# ShineRider.net
KiCad netlist of a schematic drawn in Altium Designer
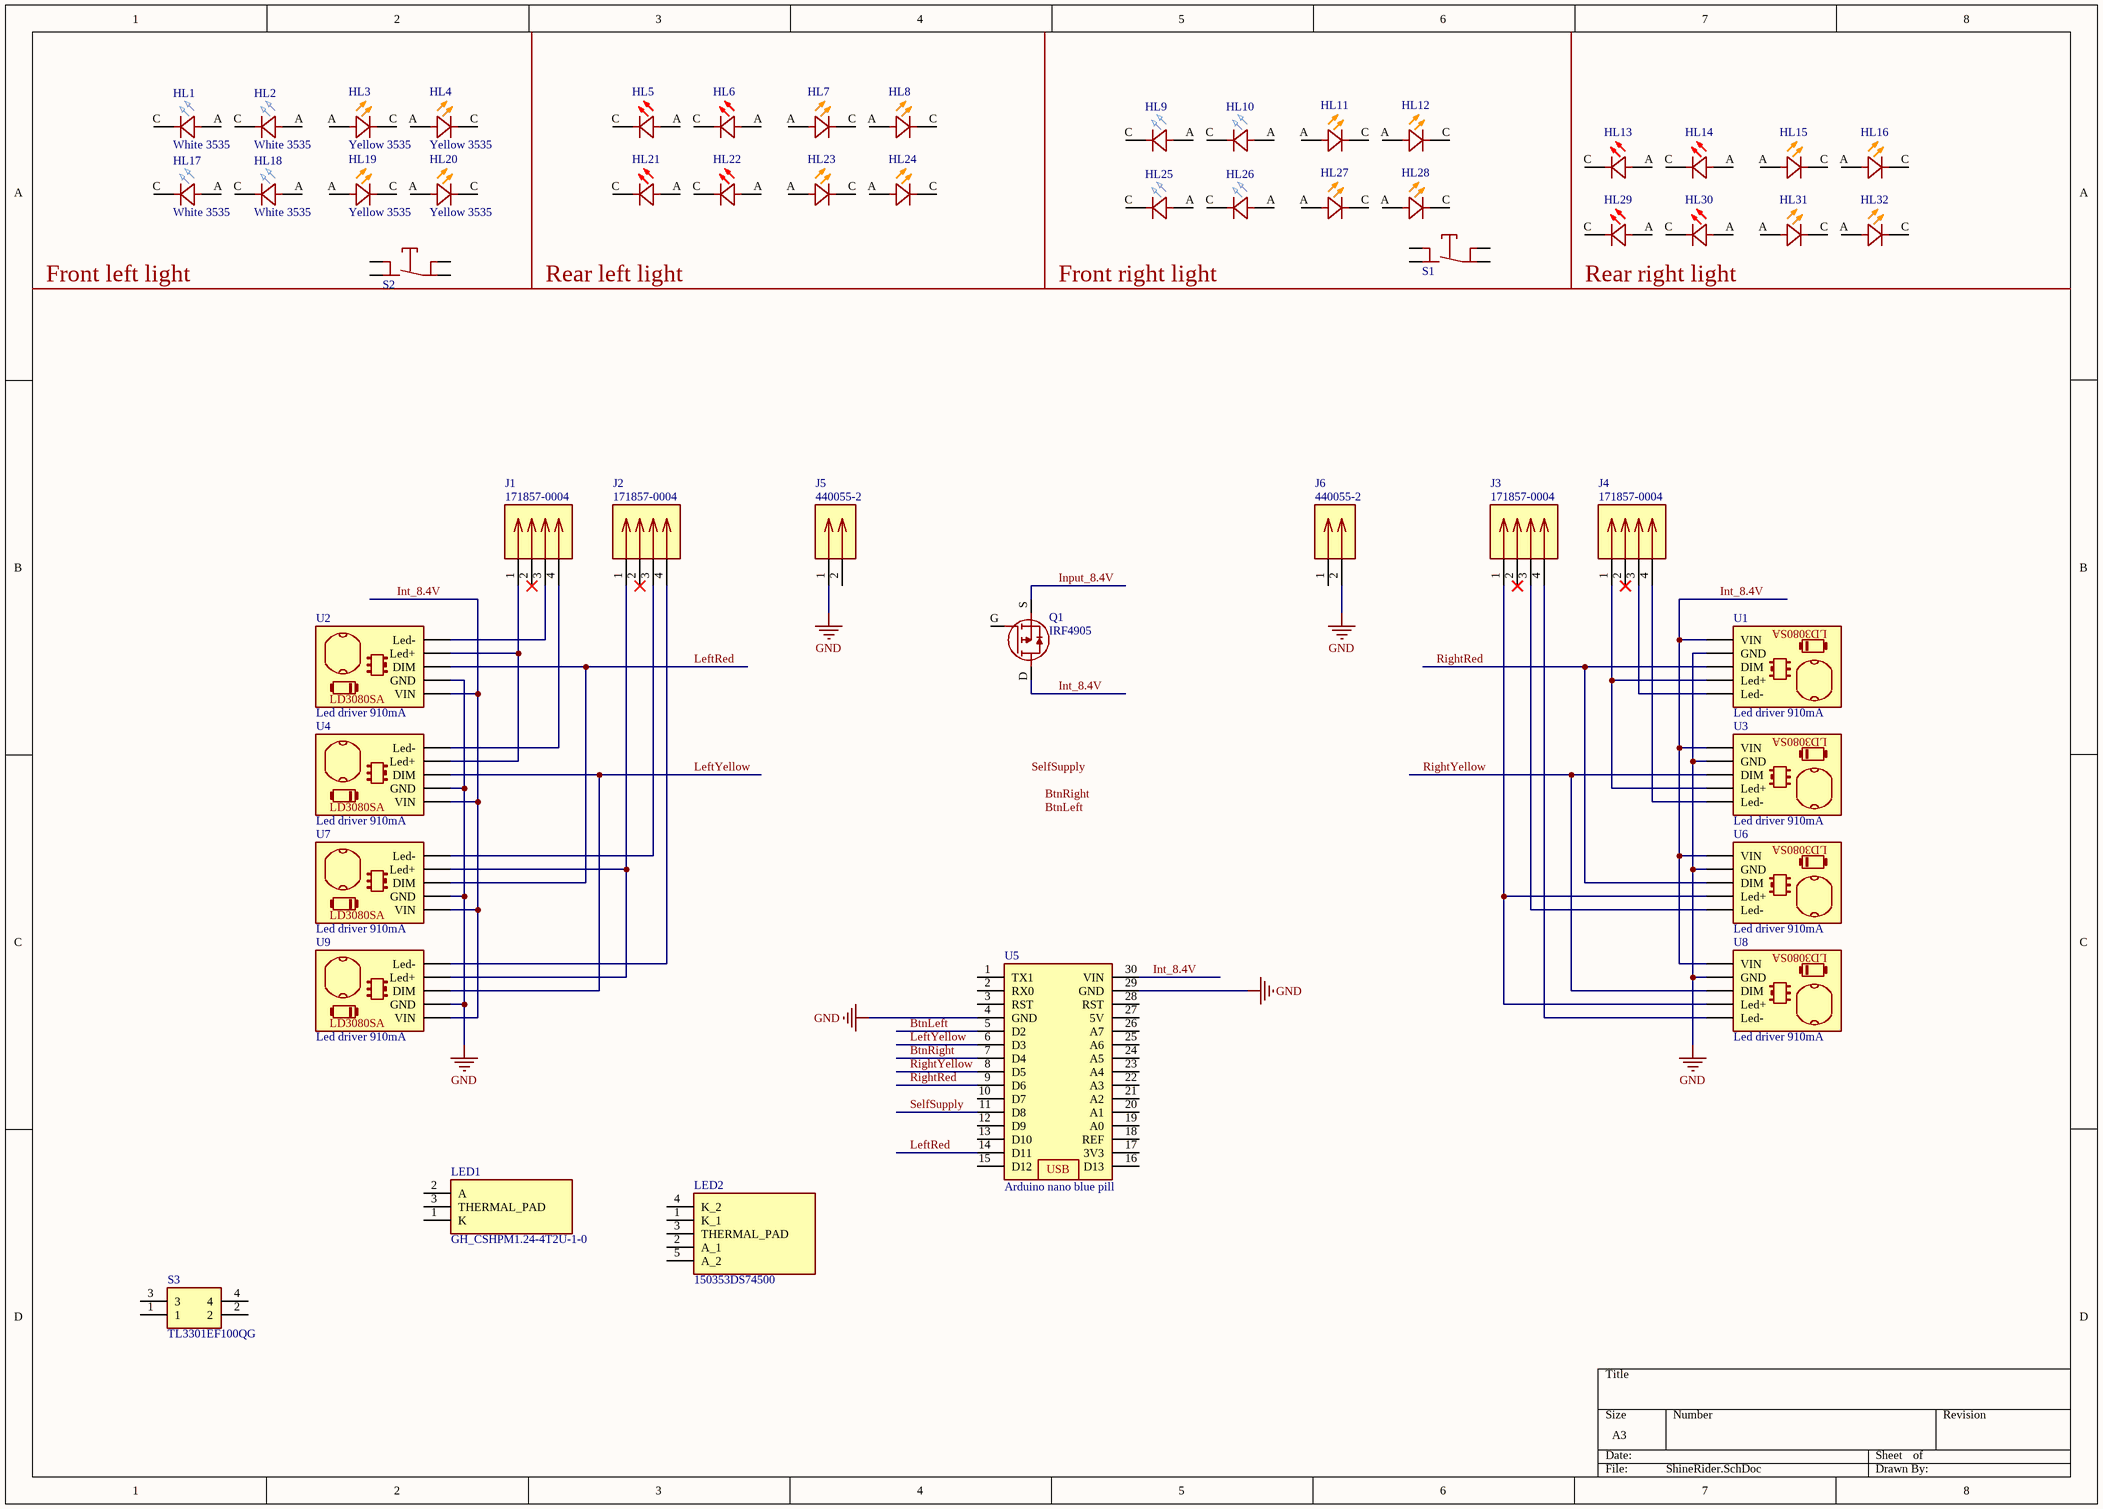
[diagram p0: ShineRider.SchDoc]

(export (version "E")
  (design (tool "Eeschema 10.0.6"))
  (components
    (comp (ref "HL1")
      (value "White 3535")
      (footprint "150353FS74500")
      (libsource (lib "SchComponents") (part "3535 white led"))
    )
    (comp (ref "HL2")
      (value "White 3535")
      (footprint "150353FS74500")
      (libsource (lib "SchComponents") (part "3535 white led"))
    )
    (comp (ref "HL3")
      (value "Yellow 3535")
      (footprint "150353FS74500")
      (libsource (lib "SchComponents") (part "3535 yellow led"))
    )
    (comp (ref "HL4")
      (value "Yellow 3535")
      (footprint "150353FS74500")
      (libsource (lib "SchComponents") (part "3535 yellow led"))
    )
    (comp (ref "HL5")
      (value "Red 3535")
      (footprint "150353FS74500")
      (libsource (lib "SchComponents") (part "3535 red led"))
    )
    (comp (ref "HL6")
      (value "Red 3535")
      (footprint "150353FS74500")
      (libsource (lib "SchComponents") (part "3535 red led"))
    )
    (comp (ref "HL7")
      (value "Yellow 3535")
      (footprint "150353FS74500")
      (libsource (lib "SchComponents") (part "3535 yellow led"))
    )
    (comp (ref "HL8")
      (value "Yellow 3535")
      (footprint "150353FS74500")
      (libsource (lib "SchComponents") (part "3535 yellow led"))
    )
    (comp (ref "HL9")
      (value "White 3535")
      (footprint "150353FS74500")
      (libsource (lib "SchComponents") (part "3535 white led"))
    )
    (comp (ref "HL10")
      (value "White 3535")
      (footprint "150353FS74500")
      (libsource (lib "SchComponents") (part "3535 white led"))
    )
    (comp (ref "HL11")
      (value "Yellow 3535")
      (footprint "150353FS74500")
      (libsource (lib "SchComponents") (part "3535 yellow led"))
    )
    (comp (ref "HL12")
      (value "Yellow 3535")
      (footprint "150353FS74500")
      (libsource (lib "SchComponents") (part "3535 yellow led"))
    )
    (comp (ref "HL13")
      (value "Red 3535")
      (footprint "150353FS74500")
      (libsource (lib "SchComponents") (part "3535 red led"))
    )
    (comp (ref "HL14")
      (value "Red 3535")
      (footprint "150353FS74500")
      (libsource (lib "SchComponents") (part "3535 red led"))
    )
    (comp (ref "HL15")
      (value "Yellow 3535")
      (footprint "150353FS74500")
      (libsource (lib "SchComponents") (part "3535 yellow led"))
    )
    (comp (ref "HL16")
      (value "Yellow 3535")
      (footprint "150353FS74500")
      (libsource (lib "SchComponents") (part "3535 yellow led"))
    )
    (comp (ref "HL17")
      (value "White 3535")
      (footprint "150353FS74500")
      (libsource (lib "SchComponents") (part "3535 white led"))
    )
    (comp (ref "HL18")
      (value "White 3535")
      (footprint "150353FS74500")
      (libsource (lib "SchComponents") (part "3535 white led"))
    )
    (comp (ref "HL19")
      (value "Yellow 3535")
      (footprint "150353FS74500")
      (libsource (lib "SchComponents") (part "3535 yellow led"))
    )
    (comp (ref "HL20")
      (value "Yellow 3535")
      (footprint "150353FS74500")
      (libsource (lib "SchComponents") (part "3535 yellow led"))
    )
    (comp (ref "HL21")
      (value "Red 3535")
      (footprint "150353FS74500")
      (libsource (lib "SchComponents") (part "3535 red led"))
    )
    (comp (ref "HL22")
      (value "Red 3535")
      (footprint "150353FS74500")
      (libsource (lib "SchComponents") (part "3535 red led"))
    )
    (comp (ref "HL23")
      (value "Yellow 3535")
      (footprint "150353FS74500")
      (libsource (lib "SchComponents") (part "3535 yellow led"))
    )
    (comp (ref "HL24")
      (value "Yellow 3535")
      (footprint "150353FS74500")
      (libsource (lib "SchComponents") (part "3535 yellow led"))
    )
    (comp (ref "HL25")
      (value "White 3535")
      (footprint "150353FS74500")
      (libsource (lib "SchComponents") (part "3535 white led"))
    )
    (comp (ref "HL26")
      (value "White 3535")
      (footprint "150353FS74500")
      (libsource (lib "SchComponents") (part "3535 white led"))
    )
    (comp (ref "HL27")
      (value "Yellow 3535")
      (footprint "150353FS74500")
      (libsource (lib "SchComponents") (part "3535 yellow led"))
    )
    (comp (ref "HL28")
      (value "Yellow 3535")
      (footprint "150353FS74500")
      (libsource (lib "SchComponents") (part "3535 yellow led"))
    )
    (comp (ref "HL29")
      (value "Red 3535")
      (footprint "150353FS74500")
      (libsource (lib "SchComponents") (part "3535 red led"))
    )
    (comp (ref "HL30")
      (value "Red 3535")
      (footprint "150353FS74500")
      (libsource (lib "SchComponents") (part "3535 red led"))
    )
    (comp (ref "HL31")
      (value "Yellow 3535")
      (footprint "150353FS74500")
      (libsource (lib "SchComponents") (part "3535 yellow led"))
    )
    (comp (ref "HL32")
      (value "Yellow 3535")
      (footprint "150353FS74500")
      (libsource (lib "SchComponents") (part "3535 yellow led"))
    )
    (comp (ref "J1")
      (value "171857-0004")
      (footprint "171857-0004")
      (fields (field (name "MOUSER PART NUMBER") "538-171857-0004"))
      (libsource (lib "SchComponents") (part "171857-0004"))
    )
    (comp (ref "J2")
      (value "171857-0004")
      (footprint "171857-0004")
      (fields (field (name "MOUSER PART NUMBER") "538-171857-0004"))
      (libsource (lib "SchComponents") (part "171857-0004"))
    )
    (comp (ref "J3")
      (value "171857-0004")
      (footprint "171857-0004")
      (fields (field (name "MOUSER PART NUMBER") "538-171857-0004"))
      (libsource (lib "SchComponents") (part "171857-0004"))
    )
    (comp (ref "J4")
      (value "171857-0004")
      (footprint "171857-0004")
      (fields (field (name "MOUSER PART NUMBER") "538-171857-0004"))
      (libsource (lib "SchComponents") (part "171857-0004"))
    )
    (comp (ref "J5")
      (value "440055-2")
      (footprint "SHDRRA2W50P0X200_1X2_600X770X525P")
      (description "Body Features: Primary Product Color Natural")
      (fields (field (name "MOUSER PART NUMBER") "571-440055-2"))
      (libsource (lib "SchComponents") (part "440055-2"))
    )
    (comp (ref "J6")
      (value "440055-2")
      (footprint "SHDRRA2W50P0X200_1X2_600X770X525P")
      (description "Body Features: Primary Product Color Natural")
      (fields (field (name "MOUSER PART NUMBER") "571-440055-2"))
      (libsource (lib "SchComponents") (part "440055-2"))
    )
    (comp (ref "LED1")
      (value "GH_CSHPM1.24-4T2U-1-0")
      (footprint "SamacSys:GHCSHPM1244T2U10")
      (description "LED")
      (fields
        (field (name "MANUFACTURER_PART_NUMBER") "GH CSHPM1.24-4T2U-1-0")
        (field (name "MOUSER PART NUMBER") "720-GHCSHPM124A9329")
      )
      (libsource (lib "*") (part "GH_CSHPM1.24-4T2U-1-0"))
    )
    (comp (ref "LED2")
      (value "150353DS74500")
      (footprint "SamacSys:150353DS74500")
      (description "LED")
      (fields (field (name "MOUSER PART NUMBER") "710-150353DS74500"))
      (libsource (lib "*") (part "150353DS74500"))
    )
    (comp (ref "Q1")
      (value "IRF4905")
      (footprint "IRF4905STRLPBF")
      (fields
        (field (name "MOUSER PART NUMBER") "942-IRF4905STRLPBF")
        (field (name "MANUFACTURER_PART_NUMBER") "IRF4905STRLPBF")
      )
      (libsource (lib "SchComponents") (part "IRF4905STRLPBF"))
    )
    (comp (ref "S1")
      (value "BTN")
      (footprint "SamacSys:TL3301EF100QG")
      (description "SWITCH TACTILE SPST-NO 0.05A")
      (fields
        (field (name "MANUFACTURER_PART_NUMBER") "TL3301EF100QG")
        (field (name "MOUSER PART NUMBER") "612-TL3301EF")
      )
      (libsource (lib "SchComponents") (part "TL3301EF100QG"))
    )
    (comp (ref "S2")
      (value "BTN")
      (footprint "SamacSys:TL3301EF100QG")
      (description "SWITCH TACTILE SPST-NO 0.05A")
      (fields
        (field (name "MANUFACTURER_PART_NUMBER") "TL3301EF100QG")
        (field (name "MOUSER PART NUMBER") "612-TL3301EF")
      )
      (libsource (lib "SchComponents") (part "TL3301EF100QG"))
    )
    (comp (ref "S3")
      (value "TL3301EF100QG")
      (footprint "SamacSys:TL3301EF100QG")
      (description "Switch")
      (fields (field (name "MOUSER PART NUMBER") "612-TL3301EF"))
      (libsource (lib "*") (part "TL3301EF100QG"))
    )
    (comp (ref "U1")
      (value "Led driver 910mA")
      (footprint "LD3080SA")
      (libsource (lib "SchComponents") (part "LD3080SA"))
    )
    (comp (ref "U2")
      (value "Led driver 910mA")
      (footprint "LD3080SA")
      (libsource (lib "") (part "LD3080SA_1"))
    )
    (comp (ref "U3")
      (value "Led driver 910mA")
      (footprint "LD3080SA")
      (libsource (lib "SchComponents") (part "LD3080SA"))
    )
    (comp (ref "U4")
      (value "Led driver 910mA")
      (footprint "LD3080SA")
      (libsource (lib "") (part "LD3080SA_1"))
    )
    (comp (ref "U5")
      (value "Arduino nano blue pill")
      (footprint "ArduinoNanoBluePill")
      (libsource (lib "SchComponents") (part "ArduinoNano"))
    )
    (comp (ref "U6")
      (value "Led driver 910mA")
      (footprint "LD3080SA")
      (libsource (lib "SchComponents") (part "LD3080SA"))
    )
    (comp (ref "U7")
      (value "Led driver 910mA")
      (footprint "LD3080SA")
      (libsource (lib "") (part "LD3080SA_1"))
    )
    (comp (ref "U8")
      (value "Led driver 910mA")
      (footprint "LD3080SA")
      (libsource (lib "SchComponents") (part "LD3080SA"))
    )
    (comp (ref "U9")
      (value "Led driver 910mA")
      (footprint "LD3080SA")
      (libsource (lib "") (part "LD3080SA_1"))
    )
  )
  (nets
    (net (code "1") (name "/BtnLeft") (class "Default")
      (node (ref "U5") (pin "5") (pinfunction "D2_5") (pintype "passive"))
    )
    (net (code "2") (name "/BtnRight") (class "Default")
      (node (ref "U5") (pin "7") (pinfunction "D4_7") (pintype "passive"))
    )
    (net (code "3") (name "/Input_8.4V") (class "Default")
      (node (ref "Q1") (pin "S") (pinfunction "S_S") (pintype "passive"))
    )
    (net (code "4") (name "/Int_8.4V") (class "Default")
      (node (ref "Q1") (pin "D") (pinfunction "D_D") (pintype "passive"))
      (node (ref "U1") (pin "1") (pinfunction "VIN_1") (pintype "passive"))
      (node (ref "U2") (pin "1") (pinfunction "VIN_1") (pintype "passive"))
      (node (ref "U3") (pin "1") (pinfunction "VIN_1") (pintype "passive"))
      (node (ref "U4") (pin "1") (pinfunction "VIN_1") (pintype "passive"))
      (node (ref "U5") (pin "30") (pinfunction "VIN_30") (pintype "passive"))
      (node (ref "U6") (pin "1") (pinfunction "VIN_1") (pintype "passive"))
      (node (ref "U7") (pin "1") (pinfunction "VIN_1") (pintype "passive"))
      (node (ref "U8") (pin "1") (pinfunction "VIN_1") (pintype "passive"))
      (node (ref "U9") (pin "1") (pinfunction "VIN_1") (pintype "passive"))
    )
    (net (code "5") (name "/LeftRed") (class "Default")
      (node (ref "U2") (pin "3") (pinfunction "DIM_3") (pintype "passive"))
      (node (ref "U5") (pin "14") (pinfunction "D11_14") (pintype "passive"))
      (node (ref "U7") (pin "3") (pinfunction "DIM_3") (pintype "passive"))
    )
    (net (code "6") (name "/LeftYellow") (class "Default")
      (node (ref "U4") (pin "3") (pinfunction "DIM_3") (pintype "passive"))
      (node (ref "U5") (pin "6") (pinfunction "D3_6") (pintype "passive"))
      (node (ref "U9") (pin "3") (pinfunction "DIM_3") (pintype "passive"))
    )
    (net (code "7") (name "/RightRed") (class "Default")
      (node (ref "U1") (pin "3") (pinfunction "DIM_3") (pintype "passive"))
      (node (ref "U5") (pin "9") (pinfunction "D6_9") (pintype "passive"))
      (node (ref "U6") (pin "3") (pinfunction "DIM_3") (pintype "passive"))
    )
    (net (code "8") (name "/RightYellow") (class "Default")
      (node (ref "U3") (pin "3") (pinfunction "DIM_3") (pintype "passive"))
      (node (ref "U5") (pin "8") (pinfunction "D5_8") (pintype "passive"))
      (node (ref "U8") (pin "3") (pinfunction "DIM_3") (pintype "passive"))
    )
    (net (code "9") (name "/SelfSupply") (class "Default")
      (node (ref "U5") (pin "11") (pinfunction "D8_11") (pintype "passive"))
    )
    (net (code "10") (name "GND") (class "Default")
      (node (ref "J5") (pin "1") (pinfunction "1_1") (pintype "passive"))
      (node (ref "J6") (pin "2") (pinfunction "2_2") (pintype "passive"))
      (node (ref "U1") (pin "2") (pinfunction "GND_2") (pintype "passive"))
      (node (ref "U2") (pin "2") (pinfunction "GND_2") (pintype "passive"))
      (node (ref "U3") (pin "2") (pinfunction "GND_2") (pintype "passive"))
      (node (ref "U4") (pin "2") (pinfunction "GND_2") (pintype "passive"))
      (node (ref "U5") (pin "29") (pinfunction "GND_29") (pintype "passive"))
      (node (ref "U5") (pin "4") (pinfunction "GND_4") (pintype "passive"))
      (node (ref "U6") (pin "2") (pinfunction "GND_2") (pintype "passive"))
      (node (ref "U7") (pin "2") (pinfunction "GND_2") (pintype "passive"))
      (node (ref "U8") (pin "2") (pinfunction "GND_2") (pintype "passive"))
      (node (ref "U9") (pin "2") (pinfunction "GND_2") (pintype "passive"))
    )
    (net (code "11") (name "Net-(U1-Led+)") (class "Default")
      (node (ref "J4") (pin "1") (pinfunction "1_1") (pintype "passive"))
      (node (ref "U1") (pin "4") (pinfunction "Led+_4") (pintype "passive"))
      (node (ref "U3") (pin "4") (pinfunction "Led+_4") (pintype "passive"))
    )
    (net (code "12") (name "Net-(U1-Led-)") (class "Default")
      (node (ref "J4") (pin "3") (pinfunction "3_3") (pintype "passive"))
      (node (ref "U1") (pin "5") (pinfunction "Led-_5") (pintype "passive"))
    )
    (net (code "13") (name "Net-(U2-Led+)") (class "Default")
      (node (ref "J1") (pin "1") (pinfunction "1_1") (pintype "passive"))
      (node (ref "U2") (pin "4") (pinfunction "Led+_4") (pintype "passive"))
      (node (ref "U4") (pin "4") (pinfunction "Led+_4") (pintype "passive"))
    )
    (net (code "14") (name "Net-(U2-Led-)") (class "Default")
      (node (ref "J1") (pin "3") (pinfunction "3_3") (pintype "passive"))
      (node (ref "U2") (pin "5") (pinfunction "Led-_5") (pintype "passive"))
    )
    (net (code "15") (name "Net-(U3-Led-)") (class "Default")
      (node (ref "J4") (pin "4") (pinfunction "4_4") (pintype "passive"))
      (node (ref "U3") (pin "5") (pinfunction "Led-_5") (pintype "passive"))
    )
    (net (code "16") (name "Net-(U4-Led-)") (class "Default")
      (node (ref "J1") (pin "4") (pinfunction "4_4") (pintype "passive"))
      (node (ref "U4") (pin "5") (pinfunction "Led-_5") (pintype "passive"))
    )
    (net (code "17") (name "Net-(U6-Led+)") (class "Default")
      (node (ref "J3") (pin "1") (pinfunction "1_1") (pintype "passive"))
      (node (ref "U6") (pin "4") (pinfunction "Led+_4") (pintype "passive"))
      (node (ref "U8") (pin "4") (pinfunction "Led+_4") (pintype "passive"))
    )
    (net (code "18") (name "Net-(U6-Led-)") (class "Default")
      (node (ref "J3") (pin "3") (pinfunction "3_3") (pintype "passive"))
      (node (ref "U6") (pin "5") (pinfunction "Led-_5") (pintype "passive"))
    )
    (net (code "19") (name "Net-(U7-Led+)") (class "Default")
      (node (ref "J2") (pin "1") (pinfunction "1_1") (pintype "passive"))
      (node (ref "U7") (pin "4") (pinfunction "Led+_4") (pintype "passive"))
      (node (ref "U9") (pin "4") (pinfunction "Led+_4") (pintype "passive"))
    )
    (net (code "20") (name "Net-(U7-Led-)") (class "Default")
      (node (ref "J2") (pin "3") (pinfunction "3_3") (pintype "passive"))
      (node (ref "U7") (pin "5") (pinfunction "Led-_5") (pintype "passive"))
    )
    (net (code "21") (name "Net-(U8-Led-)") (class "Default")
      (node (ref "J3") (pin "4") (pinfunction "4_4") (pintype "passive"))
      (node (ref "U8") (pin "5") (pinfunction "Led-_5") (pintype "passive"))
    )
    (net (code "22") (name "Net-(U9-Led-)") (class "Default")
      (node (ref "J2") (pin "4") (pinfunction "4_4") (pintype "passive"))
      (node (ref "U9") (pin "5") (pinfunction "Led-_5") (pintype "passive"))
    )
    (net (code "23") (name "unconnected-(HL1-CK-PadC)") (class "Default")
      (node (ref "HL1") (pin "C") (pinfunction "CK_C") (pintype "passive"))
    )
    (net (code "24") (name "unconnected-(HL1-PadA)") (class "Default")
      (node (ref "HL1") (pin "A") (pinfunction "A_A") (pintype "passive"))
    )
    (net (code "25") (name "unconnected-(HL2-CK-PadC)") (class "Default")
      (node (ref "HL2") (pin "C") (pinfunction "CK_C") (pintype "passive"))
    )
    (net (code "26") (name "unconnected-(HL2-PadA)") (class "Default")
      (node (ref "HL2") (pin "A") (pinfunction "A_A") (pintype "passive"))
    )
    (net (code "27") (name "unconnected-(HL3-CK-PadC)") (class "Default")
      (node (ref "HL3") (pin "C") (pinfunction "CK_C") (pintype "passive"))
    )
    (net (code "28") (name "unconnected-(HL3-PadA)") (class "Default")
      (node (ref "HL3") (pin "A") (pinfunction "A_A") (pintype "passive"))
    )
    (net (code "29") (name "unconnected-(HL4-CK-PadC)") (class "Default")
      (node (ref "HL4") (pin "C") (pinfunction "CK_C") (pintype "passive"))
    )
    (net (code "30") (name "unconnected-(HL4-PadA)") (class "Default")
      (node (ref "HL4") (pin "A") (pinfunction "A_A") (pintype "passive"))
    )
    (net (code "31") (name "unconnected-(HL5-CK-PadC)") (class "Default")
      (node (ref "HL5") (pin "C") (pinfunction "CK_C") (pintype "passive"))
    )
    (net (code "32") (name "unconnected-(HL5-PadA)") (class "Default")
      (node (ref "HL5") (pin "A") (pinfunction "A_A") (pintype "passive"))
    )
    (net (code "33") (name "unconnected-(HL6-CK-PadC)") (class "Default")
      (node (ref "HL6") (pin "C") (pinfunction "CK_C") (pintype "passive"))
    )
    (net (code "34") (name "unconnected-(HL6-PadA)") (class "Default")
      (node (ref "HL6") (pin "A") (pinfunction "A_A") (pintype "passive"))
    )
    (net (code "35") (name "unconnected-(HL7-CK-PadC)") (class "Default")
      (node (ref "HL7") (pin "C") (pinfunction "CK_C") (pintype "passive"))
    )
    (net (code "36") (name "unconnected-(HL7-PadA)") (class "Default")
      (node (ref "HL7") (pin "A") (pinfunction "A_A") (pintype "passive"))
    )
    (net (code "37") (name "unconnected-(HL8-CK-PadC)") (class "Default")
      (node (ref "HL8") (pin "C") (pinfunction "CK_C") (pintype "passive"))
    )
    (net (code "38") (name "unconnected-(HL8-PadA)") (class "Default")
      (node (ref "HL8") (pin "A") (pinfunction "A_A") (pintype "passive"))
    )
    (net (code "39") (name "unconnected-(HL9-CK-PadC)") (class "Default")
      (node (ref "HL9") (pin "C") (pinfunction "CK_C") (pintype "passive"))
    )
    (net (code "40") (name "unconnected-(HL9-PadA)") (class "Default")
      (node (ref "HL9") (pin "A") (pinfunction "A_A") (pintype "passive"))
    )
    (net (code "41") (name "unconnected-(HL10-CK-PadC)") (class "Default")
      (node (ref "HL10") (pin "C") (pinfunction "CK_C") (pintype "passive"))
    )
    (net (code "42") (name "unconnected-(HL10-PadA)") (class "Default")
      (node (ref "HL10") (pin "A") (pinfunction "A_A") (pintype "passive"))
    )
    (net (code "43") (name "unconnected-(HL11-CK-PadC)") (class "Default")
      (node (ref "HL11") (pin "C") (pinfunction "CK_C") (pintype "passive"))
    )
    (net (code "44") (name "unconnected-(HL11-PadA)") (class "Default")
      (node (ref "HL11") (pin "A") (pinfunction "A_A") (pintype "passive"))
    )
    (net (code "45") (name "unconnected-(HL12-CK-PadC)") (class "Default")
      (node (ref "HL12") (pin "C") (pinfunction "CK_C") (pintype "passive"))
    )
    (net (code "46") (name "unconnected-(HL12-PadA)") (class "Default")
      (node (ref "HL12") (pin "A") (pinfunction "A_A") (pintype "passive"))
    )
    (net (code "47") (name "unconnected-(HL13-CK-PadC)") (class "Default")
      (node (ref "HL13") (pin "C") (pinfunction "CK_C") (pintype "passive"))
    )
    (net (code "48") (name "unconnected-(HL13-PadA)") (class "Default")
      (node (ref "HL13") (pin "A") (pinfunction "A_A") (pintype "passive"))
    )
    (net (code "49") (name "unconnected-(HL14-CK-PadC)") (class "Default")
      (node (ref "HL14") (pin "C") (pinfunction "CK_C") (pintype "passive"))
    )
    (net (code "50") (name "unconnected-(HL14-PadA)") (class "Default")
      (node (ref "HL14") (pin "A") (pinfunction "A_A") (pintype "passive"))
    )
    (net (code "51") (name "unconnected-(HL15-CK-PadC)") (class "Default")
      (node (ref "HL15") (pin "C") (pinfunction "CK_C") (pintype "passive"))
    )
    (net (code "52") (name "unconnected-(HL15-PadA)") (class "Default")
      (node (ref "HL15") (pin "A") (pinfunction "A_A") (pintype "passive"))
    )
    (net (code "53") (name "unconnected-(HL16-CK-PadC)") (class "Default")
      (node (ref "HL16") (pin "C") (pinfunction "CK_C") (pintype "passive"))
    )
    (net (code "54") (name "unconnected-(HL16-PadA)") (class "Default")
      (node (ref "HL16") (pin "A") (pinfunction "A_A") (pintype "passive"))
    )
    (net (code "55") (name "unconnected-(HL17-CK-PadC)") (class "Default")
      (node (ref "HL17") (pin "C") (pinfunction "CK_C") (pintype "passive"))
    )
    (net (code "56") (name "unconnected-(HL17-PadA)") (class "Default")
      (node (ref "HL17") (pin "A") (pinfunction "A_A") (pintype "passive"))
    )
    (net (code "57") (name "unconnected-(HL18-CK-PadC)") (class "Default")
      (node (ref "HL18") (pin "C") (pinfunction "CK_C") (pintype "passive"))
    )
    (net (code "58") (name "unconnected-(HL18-PadA)") (class "Default")
      (node (ref "HL18") (pin "A") (pinfunction "A_A") (pintype "passive"))
    )
    (net (code "59") (name "unconnected-(HL19-CK-PadC)") (class "Default")
      (node (ref "HL19") (pin "C") (pinfunction "CK_C") (pintype "passive"))
    )
    (net (code "60") (name "unconnected-(HL19-PadA)") (class "Default")
      (node (ref "HL19") (pin "A") (pinfunction "A_A") (pintype "passive"))
    )
    (net (code "61") (name "unconnected-(HL20-CK-PadC)") (class "Default")
      (node (ref "HL20") (pin "C") (pinfunction "CK_C") (pintype "passive"))
    )
    (net (code "62") (name "unconnected-(HL20-PadA)") (class "Default")
      (node (ref "HL20") (pin "A") (pinfunction "A_A") (pintype "passive"))
    )
    (net (code "63") (name "unconnected-(HL21-CK-PadC)") (class "Default")
      (node (ref "HL21") (pin "C") (pinfunction "CK_C") (pintype "passive"))
    )
    (net (code "64") (name "unconnected-(HL21-PadA)") (class "Default")
      (node (ref "HL21") (pin "A") (pinfunction "A_A") (pintype "passive"))
    )
    (net (code "65") (name "unconnected-(HL22-CK-PadC)") (class "Default")
      (node (ref "HL22") (pin "C") (pinfunction "CK_C") (pintype "passive"))
    )
    (net (code "66") (name "unconnected-(HL22-PadA)") (class "Default")
      (node (ref "HL22") (pin "A") (pinfunction "A_A") (pintype "passive"))
    )
    (net (code "67") (name "unconnected-(HL23-CK-PadC)") (class "Default")
      (node (ref "HL23") (pin "C") (pinfunction "CK_C") (pintype "passive"))
    )
    (net (code "68") (name "unconnected-(HL23-PadA)") (class "Default")
      (node (ref "HL23") (pin "A") (pinfunction "A_A") (pintype "passive"))
    )
    (net (code "69") (name "unconnected-(HL24-CK-PadC)") (class "Default")
      (node (ref "HL24") (pin "C") (pinfunction "CK_C") (pintype "passive"))
    )
    (net (code "70") (name "unconnected-(HL24-PadA)") (class "Default")
      (node (ref "HL24") (pin "A") (pinfunction "A_A") (pintype "passive"))
    )
    (net (code "71") (name "unconnected-(HL25-CK-PadC)") (class "Default")
      (node (ref "HL25") (pin "C") (pinfunction "CK_C") (pintype "passive"))
    )
    (net (code "72") (name "unconnected-(HL25-PadA)") (class "Default")
      (node (ref "HL25") (pin "A") (pinfunction "A_A") (pintype "passive"))
    )
    (net (code "73") (name "unconnected-(HL26-CK-PadC)") (class "Default")
      (node (ref "HL26") (pin "C") (pinfunction "CK_C") (pintype "passive"))
    )
    (net (code "74") (name "unconnected-(HL26-PadA)") (class "Default")
      (node (ref "HL26") (pin "A") (pinfunction "A_A") (pintype "passive"))
    )
    (net (code "75") (name "unconnected-(HL27-CK-PadC)") (class "Default")
      (node (ref "HL27") (pin "C") (pinfunction "CK_C") (pintype "passive"))
    )
    (net (code "76") (name "unconnected-(HL27-PadA)") (class "Default")
      (node (ref "HL27") (pin "A") (pinfunction "A_A") (pintype "passive"))
    )
    (net (code "77") (name "unconnected-(HL28-CK-PadC)") (class "Default")
      (node (ref "HL28") (pin "C") (pinfunction "CK_C") (pintype "passive"))
    )
    (net (code "78") (name "unconnected-(HL28-PadA)") (class "Default")
      (node (ref "HL28") (pin "A") (pinfunction "A_A") (pintype "passive"))
    )
    (net (code "79") (name "unconnected-(HL29-CK-PadC)") (class "Default")
      (node (ref "HL29") (pin "C") (pinfunction "CK_C") (pintype "passive"))
    )
    (net (code "80") (name "unconnected-(HL29-PadA)") (class "Default")
      (node (ref "HL29") (pin "A") (pinfunction "A_A") (pintype "passive"))
    )
    (net (code "81") (name "unconnected-(HL30-CK-PadC)") (class "Default")
      (node (ref "HL30") (pin "C") (pinfunction "CK_C") (pintype "passive"))
    )
    (net (code "82") (name "unconnected-(HL30-PadA)") (class "Default")
      (node (ref "HL30") (pin "A") (pinfunction "A_A") (pintype "passive"))
    )
    (net (code "83") (name "unconnected-(HL31-CK-PadC)") (class "Default")
      (node (ref "HL31") (pin "C") (pinfunction "CK_C") (pintype "passive"))
    )
    (net (code "84") (name "unconnected-(HL31-PadA)") (class "Default")
      (node (ref "HL31") (pin "A") (pinfunction "A_A") (pintype "passive"))
    )
    (net (code "85") (name "unconnected-(HL32-CK-PadC)") (class "Default")
      (node (ref "HL32") (pin "C") (pinfunction "CK_C") (pintype "passive"))
    )
    (net (code "86") (name "unconnected-(HL32-PadA)") (class "Default")
      (node (ref "HL32") (pin "A") (pinfunction "A_A") (pintype "passive"))
    )
    (net (code "87") (name "unconnected-(J1-Pad2)") (class "Default")
      (node (ref "J1") (pin "2") (pinfunction "2_2") (pintype "passive+no_connect"))
    )
    (net (code "88") (name "unconnected-(J2-Pad2)") (class "Default")
      (node (ref "J2") (pin "2") (pinfunction "2_2") (pintype "passive+no_connect"))
    )
    (net (code "89") (name "unconnected-(J3-Pad2)") (class "Default")
      (node (ref "J3") (pin "2") (pinfunction "2_2") (pintype "passive+no_connect"))
    )
    (net (code "90") (name "unconnected-(J4-Pad2)") (class "Default")
      (node (ref "J4") (pin "2") (pinfunction "2_2") (pintype "passive+no_connect"))
    )
    (net (code "91") (name "unconnected-(J5-Pad2)") (class "Default")
      (node (ref "J5") (pin "2") (pinfunction "2_2") (pintype "passive"))
    )
    (net (code "92") (name "unconnected-(J6-Pad1)") (class "Default")
      (node (ref "J6") (pin "1") (pinfunction "1_1") (pintype "passive"))
    )
    (net (code "93") (name "unconnected-(LED1-A-Pad2)") (class "Default")
      (node (ref "LED1") (pin "2") (pinfunction "A_2") (pintype "passive"))
    )
    (net (code "94") (name "unconnected-(LED1-K-Pad1)") (class "Default")
      (node (ref "LED1") (pin "1") (pinfunction "K_1") (pintype "passive"))
    )
    (net (code "95") (name "unconnected-(LED1-THERMAL_PAD-Pad3)") (class "Default")
      (node (ref "LED1") (pin "3") (pinfunction "THERMAL_PAD_3") (pintype "passive"))
    )
    (net (code "96") (name "unconnected-(LED2-A_1-Pad2)") (class "Default")
      (node (ref "LED2") (pin "2") (pinfunction "A_1_2") (pintype "passive"))
    )
    (net (code "97") (name "unconnected-(LED2-A_2-Pad5)") (class "Default")
      (node (ref "LED2") (pin "5") (pinfunction "A_2_5") (pintype "passive"))
    )
    (net (code "98") (name "unconnected-(LED2-K_1-Pad1)") (class "Default")
      (node (ref "LED2") (pin "1") (pinfunction "K_1_1") (pintype "passive"))
    )
    (net (code "99") (name "unconnected-(LED2-K_2-Pad4)") (class "Default")
      (node (ref "LED2") (pin "4") (pinfunction "K_2_4") (pintype "passive"))
    )
    (net (code "100") (name "unconnected-(LED2-THERMAL_PAD-Pad3)") (class "Default")
      (node (ref "LED2") (pin "3") (pinfunction "THERMAL_PAD_3") (pintype "passive"))
    )
    (net (code "101") (name "unconnected-(Q1-PadG)") (class "Default")
      (node (ref "Q1") (pin "G") (pinfunction "G_G") (pintype "passive"))
    )
    (net (code "102") (name "unconnected-(S1-Pad1)") (class "Default")
      (node (ref "S1") (pin "1") (pinfunction "1_1") (pintype "passive"))
    )
    (net (code "103") (name "unconnected-(S1-Pad2)") (class "Default")
      (node (ref "S1") (pin "2") (pinfunction "2_2") (pintype "passive"))
    )
    (net (code "104") (name "unconnected-(S1-Pad3)") (class "Default")
      (node (ref "S1") (pin "3") (pinfunction "3_3") (pintype "passive"))
    )
    (net (code "105") (name "unconnected-(S1-Pad4)") (class "Default")
      (node (ref "S1") (pin "4") (pinfunction "4_4") (pintype "passive"))
    )
    (net (code "106") (name "unconnected-(S2-Pad1)") (class "Default")
      (node (ref "S2") (pin "1") (pinfunction "1_1") (pintype "passive"))
    )
    (net (code "107") (name "unconnected-(S2-Pad2)") (class "Default")
      (node (ref "S2") (pin "2") (pinfunction "2_2") (pintype "passive"))
    )
    (net (code "108") (name "unconnected-(S2-Pad3)") (class "Default")
      (node (ref "S2") (pin "3") (pinfunction "3_3") (pintype "passive"))
    )
    (net (code "109") (name "unconnected-(S2-Pad4)") (class "Default")
      (node (ref "S2") (pin "4") (pinfunction "4_4") (pintype "passive"))
    )
    (net (code "110") (name "unconnected-(S3-Pad1)") (class "Default")
      (node (ref "S3") (pin "1") (pinfunction "1_1") (pintype "passive"))
    )
    (net (code "111") (name "unconnected-(S3-Pad2)") (class "Default")
      (node (ref "S3") (pin "2") (pinfunction "2_2") (pintype "passive"))
    )
    (net (code "112") (name "unconnected-(S3-Pad3)") (class "Default")
      (node (ref "S3") (pin "3") (pinfunction "3_3") (pintype "passive"))
    )
    (net (code "113") (name "unconnected-(S3-Pad4)") (class "Default")
      (node (ref "S3") (pin "4") (pinfunction "4_4") (pintype "passive"))
    )
    (net (code "114") (name "unconnected-(U5-3V3-Pad17)") (class "Default")
      (node (ref "U5") (pin "17") (pinfunction "3V3_17") (pintype "passive"))
    )
    (net (code "115") (name "unconnected-(U5-5V-Pad27)") (class "Default")
      (node (ref "U5") (pin "27") (pinfunction "5V_27") (pintype "passive"))
    )
    (net (code "116") (name "unconnected-(U5-A0-Pad19)") (class "Default")
      (node (ref "U5") (pin "19") (pinfunction "A0_19") (pintype "passive"))
    )
    (net (code "117") (name "unconnected-(U5-A1-Pad20)") (class "Default")
      (node (ref "U5") (pin "20") (pinfunction "A1_20") (pintype "passive"))
    )
    (net (code "118") (name "unconnected-(U5-A2-Pad21)") (class "Default")
      (node (ref "U5") (pin "21") (pinfunction "A2_21") (pintype "passive"))
    )
    (net (code "119") (name "unconnected-(U5-A3-Pad22)") (class "Default")
      (node (ref "U5") (pin "22") (pinfunction "A3_22") (pintype "passive"))
    )
    (net (code "120") (name "unconnected-(U5-A4-Pad23)") (class "Default")
      (node (ref "U5") (pin "23") (pinfunction "A4_23") (pintype "passive"))
    )
    (net (code "121") (name "unconnected-(U5-A5-Pad24)") (class "Default")
      (node (ref "U5") (pin "24") (pinfunction "A5_24") (pintype "passive"))
    )
    (net (code "122") (name "unconnected-(U5-A6-Pad25)") (class "Default")
      (node (ref "U5") (pin "25") (pinfunction "A6_25") (pintype "passive"))
    )
    (net (code "123") (name "unconnected-(U5-A7-Pad26)") (class "Default")
      (node (ref "U5") (pin "26") (pinfunction "A7_26") (pintype "passive"))
    )
    (net (code "124") (name "unconnected-(U5-D7-Pad10)") (class "Default")
      (node (ref "U5") (pin "10") (pinfunction "D7_10") (pintype "passive"))
    )
    (net (code "125") (name "unconnected-(U5-D9-Pad12)") (class "Default")
      (node (ref "U5") (pin "12") (pinfunction "D9_12") (pintype "passive"))
    )
    (net (code "126") (name "unconnected-(U5-D10-Pad13)") (class "Default")
      (node (ref "U5") (pin "13") (pinfunction "D10_13") (pintype "passive"))
    )
    (net (code "127") (name "unconnected-(U5-D12-Pad15)") (class "Default")
      (node (ref "U5") (pin "15") (pinfunction "D12_15") (pintype "passive"))
    )
    (net (code "128") (name "unconnected-(U5-D13-Pad16)") (class "Default")
      (node (ref "U5") (pin "16") (pinfunction "D13_16") (pintype "passive"))
    )
    (net (code "129") (name "unconnected-(U5-REF-Pad18)") (class "Default")
      (node (ref "U5") (pin "18") (pinfunction "REF_18") (pintype "passive"))
    )
    (net (code "130") (name "unconnected-(U5-RST-Pad3)") (class "Default")
      (node (ref "U5") (pin "3") (pinfunction "RST_3") (pintype "passive"))
    )
    (net (code "131") (name "unconnected-(U5-RST-Pad28)") (class "Default")
      (node (ref "U5") (pin "28") (pinfunction "RST_28") (pintype "passive"))
    )
    (net (code "132") (name "unconnected-(U5-RX0-Pad2)") (class "Default")
      (node (ref "U5") (pin "2") (pinfunction "RX0_2") (pintype "passive"))
    )
    (net (code "133") (name "unconnected-(U5-TX1-Pad1)") (class "Default")
      (node (ref "U5") (pin "1") (pinfunction "TX1_1") (pintype "passive"))
    )
  )
)
